# Main.net
KiCad netlist of a schematic drawn in Altium Designer
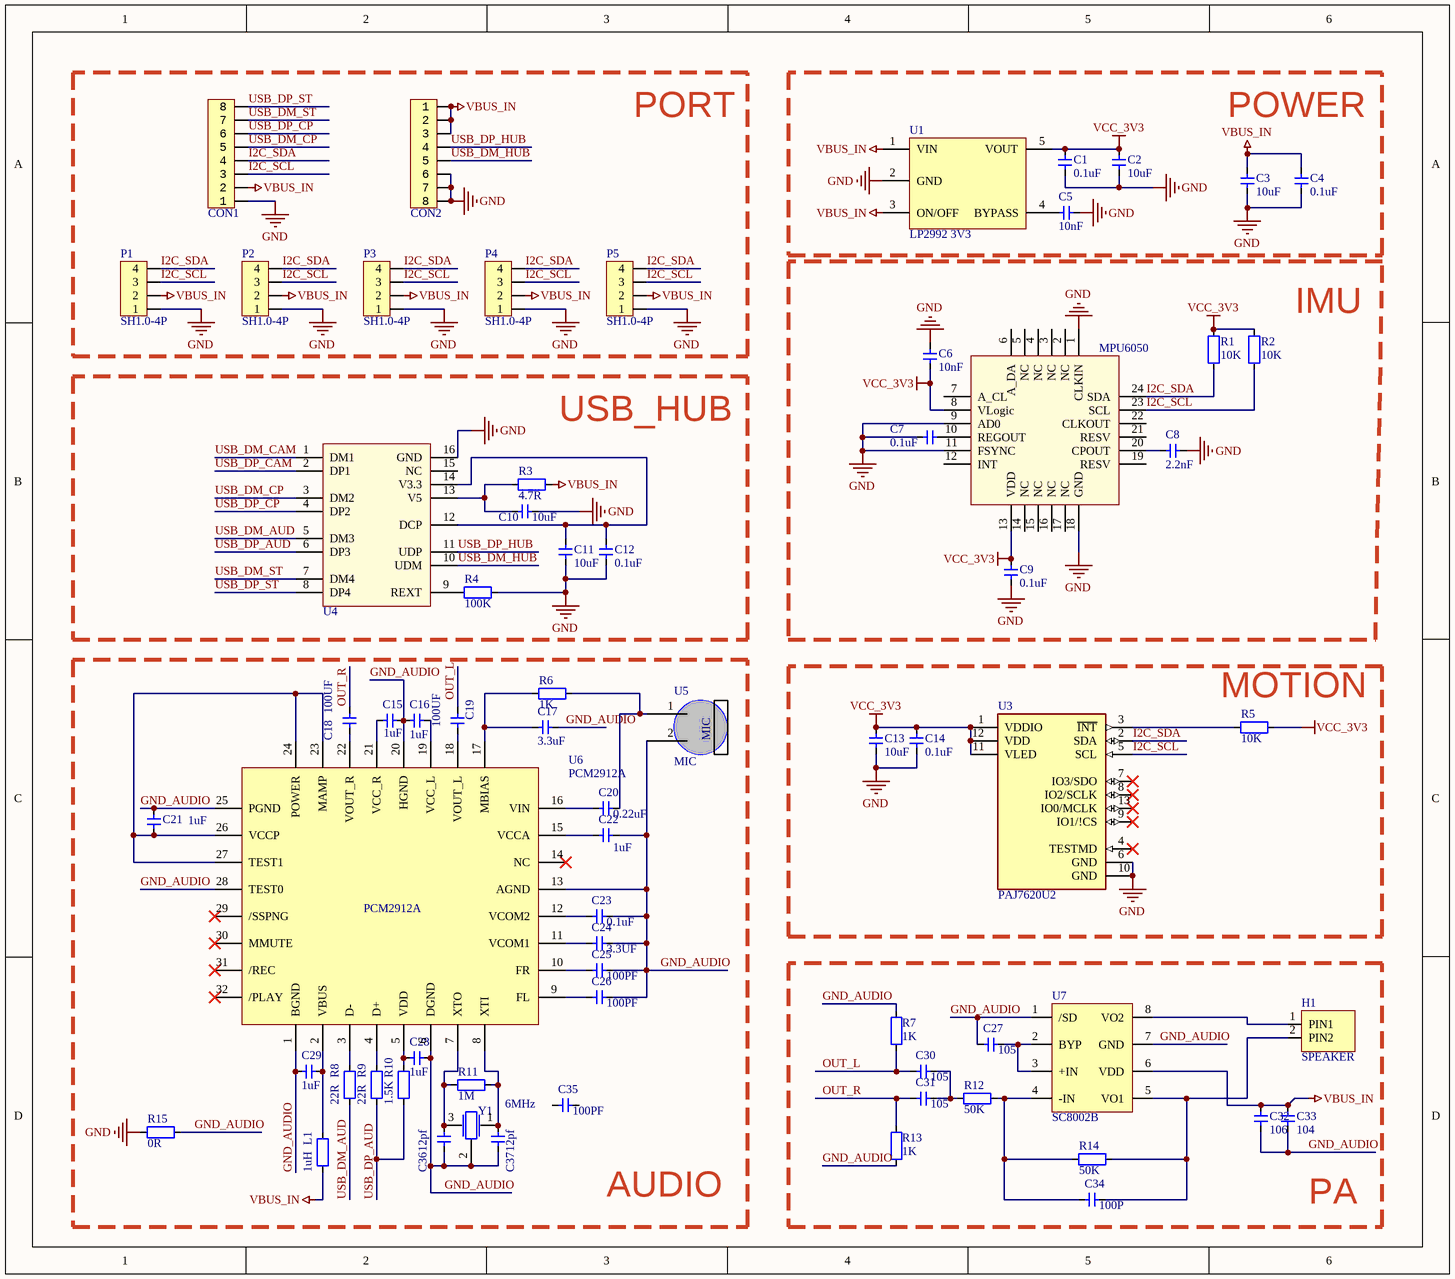
[diagram p0: Main.SchDoc]

(export (version "E")
  (design (tool "Eeschema 10.0.6"))
  (components
    (comp (ref "C1")
      (value "0.1uF")
      (footprint "SensorBoard:CAP_0402")
      (description "Capacitor")
      (libsource (lib "MyPcbLib") (part "电容-0402"))
    )
    (comp (ref "C2")
      (value "10uF")
      (footprint "SensorBoard:CAP_0402")
      (description "Capacitor")
      (libsource (lib "MyPcbLib") (part "电容-0402"))
    )
    (comp (ref "C3")
      (value "10uF")
      (footprint "SensorBoard:CAP_0402")
      (description "Capacitor")
      (libsource (lib "MyPcbLib") (part "电容-0402"))
    )
    (comp (ref "C4")
      (value "0.1uF")
      (footprint "SensorBoard:CAP_0402")
      (description "Capacitor")
      (libsource (lib "MyPcbLib") (part "电容-0402"))
    )
    (comp (ref "C5")
      (value "10nF")
      (footprint "SensorBoard:CAP_0402")
      (description "Capacitor")
      (libsource (lib "MyPcbLib") (part "电容-0402"))
    )
    (comp (ref "C6")
      (value "10nF")
      (footprint "SensorBoard:CAP_0402")
      (description "Capacitor")
      (libsource (lib "MyPcbLib") (part "电容-0402"))
    )
    (comp (ref "C7")
      (value "0.1uF")
      (footprint "SensorBoard:CAP_0402")
      (description "Capacitor")
      (libsource (lib "MyPcbLib") (part "电容-0402"))
    )
    (comp (ref "C8")
      (value "2.2nF")
      (footprint "SensorBoard:CAP_0402")
      (description "Capacitor")
      (libsource (lib "MyPcbLib") (part "电容-0402"))
    )
    (comp (ref "C9")
      (value "0.1uF")
      (footprint "SensorBoard:CAP_0402")
      (description "Capacitor")
      (libsource (lib "MyPcbLib") (part "电容-0402"))
    )
    (comp (ref "C10")
      (value "10uF")
      (footprint "SensorBoard:CAP_0402")
      (description "Capacitor")
      (libsource (lib "MyPcbLib") (part "电容-0402"))
    )
    (comp (ref "C11")
      (value "10uF")
      (footprint "SensorBoard:CAP_0402")
      (description "Capacitor")
      (libsource (lib "MyPcbLib") (part "电容-0402"))
    )
    (comp (ref "C12")
      (value "0.1uF")
      (footprint "SensorBoard:CAP_0402")
      (description "Capacitor")
      (libsource (lib "MyPcbLib") (part "电容-0402"))
    )
    (comp (ref "C13")
      (value "10uF")
      (footprint "SensorBoard:CAP_0402")
      (description "Capacitor")
      (libsource (lib "MyPcbLib") (part "电容-0402"))
    )
    (comp (ref "C14")
      (value "0.1uF")
      (footprint "SensorBoard:CAP_0402")
      (description "Capacitor")
      (libsource (lib "MyPcbLib") (part "电容-0402"))
    )
    (comp (ref "C15")
      (value "1uF")
      (footprint "SensorBoard:CAP_0402")
      (description "Capacitor")
      (libsource (lib "MyPcbLib") (part "电容-0402"))
    )
    (comp (ref "C16")
      (value "1uF")
      (footprint "SensorBoard:CAP_0402")
      (description "Capacitor")
      (libsource (lib "MyPcbLib") (part "电容-0402"))
    )
    (comp (ref "C17")
      (value "3.3uF")
      (footprint "SensorBoard:CAP_0402")
      (description "Capacitor")
      (libsource (lib "MyPcbLib") (part "电容-0402"))
    )
    (comp (ref "C18")
      (value "100UF")
      (footprint "MINI-copter:3225_C")
      (description "Capacitor")
      (libsource (lib "MyPcbLib") (part "电容-0402"))
    )
    (comp (ref "C19")
      (value "100UF")
      (footprint "MINI-copter:3225_C")
      (description "Capacitor")
      (libsource (lib "MyPcbLib") (part "电容-0402"))
    )
    (comp (ref "C20")
      (value "0.22uF")
      (footprint "SensorBoard:CAP_0402")
      (description "Capacitor")
      (libsource (lib "MyPcbLib") (part "电容-0402"))
    )
    (comp (ref "C21")
      (value "1uF")
      (footprint "SensorBoard:CAP_0402")
      (description "Capacitor")
      (libsource (lib "MyPcbLib") (part "电容-0402"))
    )
    (comp (ref "C22")
      (value "1uF")
      (footprint "SensorBoard:CAP_0402")
      (description "Capacitor")
      (libsource (lib "MyPcbLib") (part "电容-0402"))
    )
    (comp (ref "C23")
      (value "0.1uF")
      (footprint "SensorBoard:CAP_0402")
      (description "Capacitor")
      (libsource (lib "MyPcbLib") (part "电容-0402"))
    )
    (comp (ref "C24")
      (value "3.3UF")
      (footprint "SensorBoard:CAP_0402")
      (description "Capacitor")
      (libsource (lib "MyPcbLib") (part "电容-0402"))
    )
    (comp (ref "C25")
      (value "100PF")
      (footprint "SensorBoard:CAP_0402")
      (description "Capacitor")
      (libsource (lib "MyPcbLib") (part "电容-0402"))
    )
    (comp (ref "C26")
      (value "100PF")
      (footprint "SensorBoard:CAP_0402")
      (description "Capacitor")
      (libsource (lib "MyPcbLib") (part "电容-0402"))
    )
    (comp (ref "C27")
      (value "105")
      (footprint "SensorBoard:CAP_0402")
      (description "Capacitor")
      (libsource (lib "MyPcbLib") (part "电容-0402"))
    )
    (comp (ref "C28")
      (value "1uF")
      (footprint "SensorBoard:CAP_0402")
      (description "Capacitor")
      (libsource (lib "MyPcbLib") (part "电容-0402"))
    )
    (comp (ref "C29")
      (value "1uF")
      (footprint "SensorBoard:CAP_0402")
      (description "Capacitor")
      (libsource (lib "MyPcbLib") (part "电容-0402"))
    )
    (comp (ref "C30")
      (value "105")
      (footprint "SensorBoard:CAP_0402")
      (description "Capacitor")
      (libsource (lib "MyPcbLib") (part "电容-0402"))
    )
    (comp (ref "C31")
      (value "105")
      (footprint "SensorBoard:CAP_0402")
      (description "Capacitor")
      (libsource (lib "MyPcbLib") (part "电容-0402"))
    )
    (comp (ref "C32")
      (value "106")
      (footprint "SensorBoard:CAP_0402")
      (description "Capacitor")
      (libsource (lib "MyPcbLib") (part "电容-0402"))
    )
    (comp (ref "C33")
      (value "104")
      (footprint "SensorBoard:CAP_0402")
      (description "Capacitor")
      (libsource (lib "MyPcbLib") (part "电容-0402"))
    )
    (comp (ref "C34")
      (value "100P")
      (footprint "SensorBoard:CAP_0402")
      (description "Capacitor")
      (libsource (lib "MyPcbLib") (part "电容-0402"))
    )
    (comp (ref "C35")
      (value "100PF")
      (footprint "SensorBoard:CAP_0402")
      (description "Capacitor")
      (libsource (lib "MyPcbLib") (part "电容-0402"))
    )
    (comp (ref "C36")
      (value "12pf")
      (footprint "SensorBoard:CAP_0402")
      (description "Capacitor")
      (libsource (lib "MyPcbLib") (part "电容-0402"))
    )
    (comp (ref "C37")
      (value "12pf")
      (footprint "SensorBoard:CAP_0402")
      (description "Capacitor")
      (libsource (lib "MyPcbLib") (part "电容-0402"))
    )
    (comp (ref "CON1")
      (value "FFC_0.5_8")
      (footprint "SensorBoard:FFC_0.5_8")
      (description "FFC")
      (libsource (lib "KitSprout") (part "FFC_0.5_8"))
    )
    (comp (ref "CON2")
      (value "FFC_0.5_8")
      (footprint "SensorBoard:FFC_0.5_8")
      (description "FFC")
      (libsource (lib "") (part "FFC_0.5_8_1"))
    )
    (comp (ref "H1")
      (value "SPEAKER")
      (footprint "ElectronBot:header2p_1.0")
      (libsource (lib "MINI-copter") (part "HEADER-2P"))
    )
    (comp (ref "L1")
      (value "1uH")
      (footprint "SensorBoard:RES_0402")
      (description "Resistor")
      (libsource (lib "") (part "电阻-0402_2"))
    )
    (comp (ref "P1")
      (value "SH1.0-4P")
      (footprint "SensorBoard:SH1.0-4P")
      (libsource (lib "MyPcbLib") (part "SH1.0-4P"))
    )
    (comp (ref "P2")
      (value "SH1.0-4P")
      (footprint "SensorBoard:SH1.0-4P")
      (libsource (lib "MyPcbLib") (part "SH1.0-4P"))
    )
    (comp (ref "P3")
      (value "SH1.0-4P")
      (footprint "SensorBoard:SH1.0-4P")
      (libsource (lib "MyPcbLib") (part "SH1.0-4P"))
    )
    (comp (ref "P4")
      (value "SH1.0-4P")
      (footprint "SensorBoard:SH1.0-4P")
      (libsource (lib "MyPcbLib") (part "SH1.0-4P"))
    )
    (comp (ref "P5")
      (value "SH1.0-4P")
      (footprint "SensorBoard:SH1.0-4P")
      (libsource (lib "MyPcbLib") (part "SH1.0-4P"))
    )
    (comp (ref "R1")
      (value "10K")
      (footprint "SensorBoard:RES_0402")
      (description "Resistor")
      (libsource (lib "") (part "电阻-0402_1"))
    )
    (comp (ref "R2")
      (value "10K")
      (footprint "SensorBoard:RES_0402")
      (description "Resistor")
      (libsource (lib "") (part "电阻-0402_1"))
    )
    (comp (ref "R3")
      (value "4.7R")
      (footprint "SensorBoard:RES_0402")
      (description "Resistor")
      (libsource (lib "") (part "电阻-0402_3"))
    )
    (comp (ref "R4")
      (value "100K")
      (footprint "SensorBoard:RES_0402")
      (description "Resistor")
      (libsource (lib "") (part "电阻-0402_3"))
    )
    (comp (ref "R5")
      (value "10K")
      (footprint "SensorBoard:RES_0402")
      (description "Resistor")
      (libsource (lib "MyPcbLib") (part "电阻-0402"))
    )
    (comp (ref "R6")
      (value "1K")
      (footprint "SensorBoard:RES_0402")
      (description "Resistor")
      (libsource (lib "MyPcbLib") (part "电阻-0402"))
    )
    (comp (ref "R7")
      (value "1K")
      (footprint "SensorBoard:RES_0402")
      (description "Resistor")
      (libsource (lib "") (part "电阻-0402_2"))
    )
    (comp (ref "R8")
      (value "22R")
      (footprint "SensorBoard:RES_0402")
      (description "Resistor")
      (libsource (lib "") (part "电阻-0402_2"))
    )
    (comp (ref "R9")
      (value "22R")
      (footprint "SensorBoard:RES_0402")
      (description "Resistor")
      (libsource (lib "") (part "电阻-0402_2"))
    )
    (comp (ref "R10")
      (value "1.5K")
      (footprint "SensorBoard:RES_0402")
      (description "Resistor")
      (libsource (lib "") (part "电阻-0402_2"))
    )
    (comp (ref "R11")
      (value "1M")
      (footprint "SensorBoard:RES_0402")
      (description "Resistor")
      (libsource (lib "MyPcbLib") (part "电阻-0402"))
    )
    (comp (ref "R12")
      (value "50K")
      (footprint "SensorBoard:RES_0402")
      (description "Resistor")
      (libsource (lib "MyPcbLib") (part "电阻-0402"))
    )
    (comp (ref "R13")
      (value "1K")
      (footprint "SensorBoard:RES_0402")
      (description "Resistor")
      (libsource (lib "") (part "电阻-0402_1"))
    )
    (comp (ref "R14")
      (value "50K")
      (footprint "SensorBoard:RES_0402")
      (description "Resistor")
      (libsource (lib "MyPcbLib") (part "电阻-0402"))
    )
    (comp (ref "R15")
      (value "0R")
      (footprint "SensorBoard:RES_0402")
      (description "Resistor")
      (libsource (lib "MyPcbLib") (part "电阻-0402"))
    )
    (comp (ref "U1")
      (value "LP2992 3V3")
      (footprint "SensorBoard:SOT23-5")
      (description "LDO")
      (libsource (lib "MyPcbLib") (part "LP2992"))
    )
    (comp (ref "U2")
      (value "MPU6050")
      (footprint "QFN-24")
      (description "六轴传感器")
      (libsource (lib "mLib") (part "MPU6050"))
    )
    (comp (ref "U3")
      (value "PAJ7620U2")
      (footprint "SensorBoard:PAJ7620U2")
      (description "module sensorPAJ7620U2 : 54/TRAY, 5400/BOX, 32400/CARTON")
      (fields (field (name "MF") "Pixart"))
      (libsource (lib "MyPcbLib") (part "PAJ7620U2"))
    )
    (comp (ref "U4")
      (value "HS8836A")
      (footprint "SensorBoard:SO-16N")
      (description "USB2.0 HUB")
      (libsource (lib "MyPcbLib") (part "HS8836A"))
    )
    (comp (ref "U5") (value "MIC") (footprint "Voice:MIC6*2.2") (libsource (lib "voice") (part "MIC")))
    (comp (ref "U6")
      (value "PCM2912A")
      (footprint "Voice:PCM2912")
      (libsource (lib "voice") (part "PCM2912A"))
    )
    (comp (ref "U7") (value "SC8002B") (footprint "Voice:SOP-8") (libsource (lib "voice") (part "SC8002B")))
    (comp (ref "Y1")
      (value "6MHz")
      (footprint "MINI-copter:cystal-3P -4520")
      (description "村田贴片")
      (libsource (lib "MyPcbLib") (part "晶振-3Pin"))
    )
  )
  (nets
    (net (code "2") (name "/GND_AUDIO") (class "Default")
      (node (ref "C15") (pin "2") (pinfunction "2_2") (pintype "passive"))
      (node (ref "C16") (pin "2") (pinfunction "2_2") (pintype "passive"))
      (node (ref "C17") (pin "2") (pinfunction "2_2") (pintype "passive"))
      (node (ref "C21") (pin "2") (pinfunction "2_2") (pintype "passive"))
      (node (ref "C22") (pin "2") (pinfunction "2_2") (pintype "passive"))
      (node (ref "C23") (pin "1") (pinfunction "1_1") (pintype "passive"))
      (node (ref "C24") (pin "1") (pinfunction "1_1") (pintype "passive"))
      (node (ref "C25") (pin "1") (pinfunction "1_1") (pintype "passive"))
      (node (ref "C26") (pin "1") (pinfunction "1_1") (pintype "passive"))
      (node (ref "C27") (pin "2") (pinfunction "2_2") (pintype "passive"))
      (node (ref "C28") (pin "1") (pinfunction "1_1") (pintype "passive"))
      (node (ref "C29") (pin "2") (pinfunction "2_2") (pintype "passive"))
      (node (ref "C32") (pin "2") (pinfunction "2_2") (pintype "passive"))
      (node (ref "C33") (pin "2") (pinfunction "2_2") (pintype "passive"))
      (node (ref "C36") (pin "2") (pinfunction "2_2") (pintype "passive"))
      (node (ref "C37") (pin "2") (pinfunction "2_2") (pintype "passive"))
      (node (ref "R13") (pin "1") (pinfunction "1_1") (pintype "passive"))
      (node (ref "R15") (pin "2") (pinfunction "2_2") (pintype "passive"))
      (node (ref "R7") (pin "1") (pinfunction "1_1") (pintype "passive"))
      (node (ref "U5") (pin "2") (pintype "passive"))
      (node (ref "U6") (pin "1") (pinfunction "BGND_1") (pintype "passive"))
      (node (ref "U6") (pin "13") (pinfunction "AGND_13") (pintype "passive"))
      (node (ref "U6") (pin "20") (pinfunction "HGND_20") (pintype "passive"))
      (node (ref "U6") (pin "25") (pinfunction "PGND_25") (pintype "passive"))
      (node (ref "U6") (pin "28") (pinfunction "TEST0_28") (pintype "passive"))
      (node (ref "U6") (pin "6") (pinfunction "DGND_6") (pintype "passive"))
      (node (ref "U7") (pin "1") (pinfunction "/SD_1") (pintype "passive"))
      (node (ref "U7") (pin "7") (pinfunction "GND_7") (pintype "passive"))
      (node (ref "Y1") (pin "2") (pinfunction "2_2") (pintype "passive"))
    )
    (net (code "3") (name "/I2C_SCL") (class "Default")
      (node (ref "CON1") (pin "3") (pinfunction "3_3") (pintype "passive"))
      (node (ref "P1") (pin "3") (pinfunction "3_3") (pintype "passive"))
      (node (ref "P2") (pin "3") (pinfunction "3_3") (pintype "passive"))
      (node (ref "P3") (pin "3") (pinfunction "3_3") (pintype "passive"))
      (node (ref "P4") (pin "3") (pinfunction "3_3") (pintype "passive"))
      (node (ref "P5") (pin "3") (pinfunction "3_3") (pintype "passive"))
      (node (ref "R2") (pin "1") (pinfunction "1_1") (pintype "passive"))
      (node (ref "U2") (pin "23") (pinfunction "SCL_23") (pintype "passive"))
      (node (ref "U3") (pin "5") (pinfunction "SCL_5") (pintype "input"))
    )
    (net (code "4") (name "/I2C_SDA") (class "Default")
      (node (ref "CON1") (pin "4") (pinfunction "4_4") (pintype "passive"))
      (node (ref "P1") (pin "4") (pinfunction "4_4") (pintype "passive"))
      (node (ref "P2") (pin "4") (pinfunction "4_4") (pintype "passive"))
      (node (ref "P3") (pin "4") (pinfunction "4_4") (pintype "passive"))
      (node (ref "P4") (pin "4") (pinfunction "4_4") (pintype "passive"))
      (node (ref "P5") (pin "4") (pinfunction "4_4") (pintype "passive"))
      (node (ref "R1") (pin "1") (pinfunction "1_1") (pintype "passive"))
      (node (ref "U2") (pin "24") (pinfunction "SDA_24") (pintype "passive"))
      (node (ref "U3") (pin "2") (pinfunction "SDA_2") (pintype "bidirectional"))
    )
    (net (code "5") (name "/OUT_L") (class "Default")
      (node (ref "C19") (pin "2") (pinfunction "2_2") (pintype "passive"))
      (node (ref "C30") (pin "2") (pinfunction "2_2") (pintype "passive"))
      (node (ref "R7") (pin "2") (pinfunction "2_2") (pintype "passive"))
    )
    (net (code "6") (name "/OUT_R") (class "Default")
      (node (ref "C18") (pin "2") (pinfunction "2_2") (pintype "passive"))
      (node (ref "C31") (pin "2") (pinfunction "2_2") (pintype "passive"))
      (node (ref "R13") (pin "2") (pinfunction "2_2") (pintype "passive"))
    )
    (net (code "7") (name "/USB_DM_AUD") (class "Default")
      (node (ref "R8") (pin "2") (pinfunction "2_2") (pintype "passive"))
      (node (ref "U4") (pin "5") (pinfunction "DM3_5") (pintype "passive"))
    )
    (net (code "8") (name "/USB_DM_CAM") (class "Default")
      (node (ref "U4") (pin "1") (pinfunction "DM1_1") (pintype "passive"))
    )
    (net (code "9") (name "/USB_DM_CP") (class "Default")
      (node (ref "CON1") (pin "5") (pinfunction "5_5") (pintype "passive"))
      (node (ref "U4") (pin "3") (pinfunction "DM2_3") (pintype "passive"))
    )
    (net (code "10") (name "/USB_DM_HUB") (class "Default")
      (node (ref "CON2") (pin "5") (pinfunction "5_5") (pintype "passive"))
      (node (ref "U4") (pin "10") (pinfunction "UDM_10") (pintype "passive"))
    )
    (net (code "11") (name "/USB_DM_ST") (class "Default")
      (node (ref "CON1") (pin "7") (pinfunction "7_7") (pintype "passive"))
      (node (ref "U4") (pin "7") (pinfunction "DM4_7") (pintype "passive"))
    )
    (net (code "12") (name "/USB_DP_AUD") (class "Default")
      (node (ref "R10") (pin "2") (pinfunction "2_2") (pintype "passive"))
      (node (ref "R9") (pin "2") (pinfunction "2_2") (pintype "passive"))
      (node (ref "U4") (pin "6") (pinfunction "DP3_6") (pintype "passive"))
    )
    (net (code "13") (name "/USB_DP_CAM") (class "Default")
      (node (ref "U4") (pin "2") (pinfunction "DP1_2") (pintype "passive"))
    )
    (net (code "14") (name "/USB_DP_CP") (class "Default")
      (node (ref "CON1") (pin "6") (pinfunction "6_6") (pintype "passive"))
      (node (ref "U4") (pin "4") (pinfunction "DP2_4") (pintype "passive"))
    )
    (net (code "15") (name "/USB_DP_HUB") (class "Default")
      (node (ref "CON2") (pin "4") (pinfunction "4_4") (pintype "passive"))
      (node (ref "U4") (pin "11") (pinfunction "UDP_11") (pintype "passive"))
    )
    (net (code "16") (name "/USB_DP_ST") (class "Default")
      (node (ref "CON1") (pin "8") (pinfunction "8_8") (pintype "passive"))
      (node (ref "U4") (pin "8") (pinfunction "DP4_8") (pintype "passive"))
    )
    (net (code "17") (name "GND") (class "Default")
      (node (ref "C1") (pin "1") (pinfunction "1_1") (pintype "passive"))
      (node (ref "C10") (pin "1") (pinfunction "1_1") (pintype "passive"))
      (node (ref "C11") (pin "2") (pinfunction "2_2") (pintype "passive"))
      (node (ref "C12") (pin "2") (pinfunction "2_2") (pintype "passive"))
      (node (ref "C13") (pin "2") (pinfunction "2_2") (pintype "passive"))
      (node (ref "C14") (pin "2") (pinfunction "2_2") (pintype "passive"))
      (node (ref "C2") (pin "1") (pinfunction "1_1") (pintype "passive"))
      (node (ref "C3") (pin "1") (pinfunction "1_1") (pintype "passive"))
      (node (ref "C4") (pin "1") (pinfunction "1_1") (pintype "passive"))
      (node (ref "C5") (pin "1") (pinfunction "1_1") (pintype "passive"))
      (node (ref "C6") (pin "2") (pinfunction "2_2") (pintype "passive"))
      (node (ref "C7") (pin "2") (pinfunction "2_2") (pintype "passive"))
      (node (ref "C8") (pin "1") (pinfunction "1_1") (pintype "passive"))
      (node (ref "C9") (pin "1") (pinfunction "1_1") (pintype "passive"))
      (node (ref "CON1") (pin "1") (pinfunction "1_1") (pintype "passive"))
      (node (ref "CON2") (pin "6") (pinfunction "6_6") (pintype "passive"))
      (node (ref "CON2") (pin "7") (pinfunction "7_7") (pintype "passive"))
      (node (ref "CON2") (pin "8") (pinfunction "8_8") (pintype "passive"))
      (node (ref "P1") (pin "1") (pinfunction "1_1") (pintype "passive"))
      (node (ref "P2") (pin "1") (pinfunction "1_1") (pintype "passive"))
      (node (ref "P3") (pin "1") (pinfunction "1_1") (pintype "passive"))
      (node (ref "P4") (pin "1") (pinfunction "1_1") (pintype "passive"))
      (node (ref "P5") (pin "1") (pinfunction "1_1") (pintype "passive"))
      (node (ref "R15") (pin "1") (pinfunction "1_1") (pintype "passive"))
      (node (ref "R4") (pin "1") (pinfunction "1_1") (pintype "passive"))
      (node (ref "U1") (pin "2") (pinfunction "GND_2") (pintype "passive"))
      (node (ref "U2") (pin "1") (pinfunction "CLKIN_1") (pintype "passive"))
      (node (ref "U2") (pin "11") (pinfunction "FSYNC_11") (pintype "passive"))
      (node (ref "U2") (pin "18") (pinfunction "GND_18") (pintype "passive"))
      (node (ref "U2") (pin "9") (pinfunction "AD0_9") (pintype "passive"))
      (node (ref "U3") (pin "10") (pinfunction "GND_10") (pintype "passive"))
      (node (ref "U3") (pin "6") (pinfunction "GND_6") (pintype "passive"))
      (node (ref "U4") (pin "16") (pinfunction "GND_16") (pintype "passive"))
    )
    (net (code "18") (name "Net-(C20-Pad2)") (class "Default")
      (node (ref "C20") (pin "2") (pinfunction "2_2") (pintype "passive"))
      (node (ref "R6") (pin "2") (pinfunction "2_2") (pintype "passive"))
      (node (ref "U5") (pin "1") (pintype "passive"))
    )
    (net (code "19") (name "Net-(C30-Pad1)") (class "Default")
      (node (ref "C30") (pin "1") (pinfunction "1_1") (pintype "passive"))
      (node (ref "C31") (pin "1") (pinfunction "1_1") (pintype "passive"))
      (node (ref "R12") (pin "1") (pinfunction "1_1") (pintype "passive"))
    )
    (net (code "20") (name "Net-(H1-PIN1)") (class "Default")
      (node (ref "H1") (pin "1") (pinfunction "PIN1_1") (pintype "passive"))
      (node (ref "U7") (pin "8") (pinfunction "VO2_8") (pintype "passive"))
    )
    (net (code "21") (name "Net-(H1-PIN2)") (class "Default")
      (node (ref "C34") (pin "1") (pinfunction "1_1") (pintype "passive"))
      (node (ref "H1") (pin "2") (pinfunction "PIN2_2") (pintype "passive"))
      (node (ref "R14") (pin "2") (pinfunction "2_2") (pintype "passive"))
      (node (ref "U7") (pin "5") (pinfunction "VO1_5") (pintype "passive"))
    )
    (net (code "22") (name "Net-(U1-BYPASS)") (class "Default")
      (node (ref "C5") (pin "2") (pinfunction "2_2") (pintype "passive"))
      (node (ref "U1") (pin "4") (pinfunction "BYPASS_4") (pintype "passive"))
    )
    (net (code "23") (name "Net-(U2-CPOUT)") (class "Default")
      (node (ref "C8") (pin "2") (pinfunction "2_2") (pintype "passive"))
      (node (ref "U2") (pin "20") (pinfunction "CPOUT_20") (pintype "passive"))
    )
    (net (code "24") (name "Net-(U2-REGOUT)") (class "Default")
      (node (ref "C7") (pin "1") (pinfunction "1_1") (pintype "passive"))
      (node (ref "U2") (pin "10") (pinfunction "REGOUT_10") (pintype "passive"))
    )
    (net (code "25") (name "Net-(U3-~{INT})") (class "Default")
      (node (ref "R5") (pin "1") (pinfunction "1_1") (pintype "passive"))
      (node (ref "U3") (pin "3") (pinfunction "~{INT}_3") (pintype "output"))
    )
    (net (code "26") (name "Net-(U4-DCP)") (class "Default")
      (node (ref "C11") (pin "1") (pinfunction "1_1") (pintype "passive"))
      (node (ref "C12") (pin "1") (pinfunction "1_1") (pintype "passive"))
      (node (ref "U4") (pin "12") (pinfunction "DCP_12") (pintype "passive"))
      (node (ref "U4") (pin "14") (pinfunction "V3.3_14") (pintype "passive"))
    )
    (net (code "27") (name "Net-(U4-REXT)") (class "Default")
      (node (ref "R4") (pin "2") (pinfunction "2_2") (pintype "passive"))
      (node (ref "U4") (pin "9") (pinfunction "REXT_9") (pintype "passive"))
    )
    (net (code "28") (name "Net-(U4-V5)") (class "Default")
      (node (ref "C10") (pin "2") (pinfunction "2_2") (pintype "passive"))
      (node (ref "R3") (pin "2") (pinfunction "2_2") (pintype "passive"))
      (node (ref "U4") (pin "13") (pinfunction "V5_13") (pintype "passive"))
    )
    (net (code "29") (name "Net-(U6-D+)") (class "Default")
      (node (ref "R9") (pin "1") (pinfunction "1_1") (pintype "passive"))
      (node (ref "U6") (pin "4") (pinfunction "D+_4") (pintype "passive"))
    )
    (net (code "30") (name "Net-(U6-D-)") (class "Default")
      (node (ref "R8") (pin "1") (pinfunction "1_1") (pintype "passive"))
      (node (ref "U6") (pin "3") (pinfunction "D-_3") (pintype "passive"))
    )
    (net (code "31") (name "Net-(U6-FL)") (class "Default")
      (node (ref "C26") (pin "2") (pinfunction "2_2") (pintype "passive"))
      (node (ref "U6") (pin "9") (pinfunction "FL_9") (pintype "passive"))
    )
    (net (code "32") (name "Net-(U6-FR)") (class "Default")
      (node (ref "C25") (pin "2") (pinfunction "2_2") (pintype "passive"))
      (node (ref "U6") (pin "10") (pinfunction "FR_10") (pintype "passive"))
    )
    (net (code "33") (name "Net-(U6-MAMP)") (class "Default")
      (node (ref "C21") (pin "1") (pinfunction "1_1") (pintype "passive"))
      (node (ref "U6") (pin "23") (pinfunction "MAMP_23") (pintype "passive"))
      (node (ref "U6") (pin "24") (pinfunction "POWER_24") (pintype "passive"))
      (node (ref "U6") (pin "26") (pinfunction "VCCP_26") (pintype "passive"))
      (node (ref "U6") (pin "27") (pinfunction "TEST1_27") (pintype "passive"))
    )
    (net (code "34") (name "Net-(U6-MBIAS)") (class "Default")
      (node (ref "C17") (pin "1") (pinfunction "1_1") (pintype "passive"))
      (node (ref "R6") (pin "1") (pinfunction "1_1") (pintype "passive"))
      (node (ref "U6") (pin "17") (pinfunction "MBIAS_17") (pintype "passive"))
    )
    (net (code "35") (name "Net-(U6-VBUS)") (class "Default")
      (node (ref "C29") (pin "1") (pinfunction "1_1") (pintype "passive"))
      (node (ref "L1") (pin "1") (pinfunction "1_1") (pintype "passive"))
      (node (ref "U6") (pin "2") (pinfunction "VBUS_2") (pintype "passive"))
    )
    (net (code "36") (name "Net-(U6-VCCA)") (class "Default")
      (node (ref "C22") (pin "1") (pinfunction "1_1") (pintype "passive"))
      (node (ref "U6") (pin "15") (pinfunction "VCCA_15") (pintype "passive"))
    )
    (net (code "37") (name "Net-(U6-VCC_L)") (class "Default")
      (node (ref "C16") (pin "1") (pinfunction "1_1") (pintype "passive"))
      (node (ref "U6") (pin "19") (pinfunction "VCC_L_19") (pintype "passive"))
    )
    (net (code "38") (name "Net-(U6-VCC_R)") (class "Default")
      (node (ref "C15") (pin "1") (pinfunction "1_1") (pintype "passive"))
      (node (ref "U6") (pin "21") (pinfunction "VCC_R_21") (pintype "passive"))
    )
    (net (code "39") (name "Net-(U6-VCOM1)") (class "Default")
      (node (ref "C24") (pin "2") (pinfunction "2_2") (pintype "passive"))
      (node (ref "U6") (pin "11") (pinfunction "VCOM1_11") (pintype "passive"))
    )
    (net (code "40") (name "Net-(U6-VCOM2)") (class "Default")
      (node (ref "C23") (pin "2") (pinfunction "2_2") (pintype "passive"))
      (node (ref "U6") (pin "12") (pinfunction "VCOM2_12") (pintype "passive"))
    )
    (net (code "41") (name "Net-(U6-VDD)") (class "Default")
      (node (ref "C28") (pin "2") (pinfunction "2_2") (pintype "passive"))
      (node (ref "R10") (pin "1") (pinfunction "1_1") (pintype "passive"))
      (node (ref "U6") (pin "5") (pinfunction "VDD_5") (pintype "passive"))
    )
    (net (code "42") (name "Net-(U6-VIN)") (class "Default")
      (node (ref "C20") (pin "1") (pinfunction "1_1") (pintype "passive"))
      (node (ref "U6") (pin "16") (pinfunction "VIN_16") (pintype "passive"))
    )
    (net (code "43") (name "Net-(U6-VOUT_L)") (class "Default")
      (node (ref "C19") (pin "1") (pinfunction "1_1") (pintype "passive"))
      (node (ref "U6") (pin "18") (pinfunction "VOUT_L_18") (pintype "passive"))
    )
    (net (code "44") (name "Net-(U6-VOUT_R)") (class "Default")
      (node (ref "C18") (pin "1") (pinfunction "1_1") (pintype "passive"))
      (node (ref "U6") (pin "22") (pinfunction "VOUT_R_22") (pintype "passive"))
    )
    (net (code "45") (name "Net-(U6-XTI)") (class "Default")
      (node (ref "C37") (pin "1") (pinfunction "1_1") (pintype "passive"))
      (node (ref "R11") (pin "2") (pinfunction "2_2") (pintype "passive"))
      (node (ref "U6") (pin "8") (pinfunction "XTI_8") (pintype "passive"))
      (node (ref "Y1") (pin "1") (pinfunction "1_1") (pintype "passive"))
    )
    (net (code "46") (name "Net-(U6-XTO)") (class "Default")
      (node (ref "C36") (pin "1") (pinfunction "1_1") (pintype "passive"))
      (node (ref "R11") (pin "1") (pinfunction "1_1") (pintype "passive"))
      (node (ref "U6") (pin "7") (pinfunction "XTO_7") (pintype "passive"))
      (node (ref "Y1") (pin "3") (pinfunction "3_3") (pintype "passive"))
    )
    (net (code "47") (name "Net-(U7-+IN)") (class "Default")
      (node (ref "C27") (pin "1") (pinfunction "1_1") (pintype "passive"))
      (node (ref "U7") (pin "2") (pinfunction "BYP_2") (pintype "passive"))
      (node (ref "U7") (pin "3") (pinfunction "+IN_3") (pintype "passive"))
    )
    (net (code "48") (name "Net-(U7--IN)") (class "Default")
      (node (ref "C34") (pin "2") (pinfunction "2_2") (pintype "passive"))
      (node (ref "R12") (pin "2") (pinfunction "2_2") (pintype "passive"))
      (node (ref "R14") (pin "1") (pinfunction "1_1") (pintype "passive"))
      (node (ref "U7") (pin "4") (pinfunction "-IN_4") (pintype "passive"))
    )
    (net (code "49") (name "VBUS_IN") (class "Default")
      (node (ref "C3") (pin "2") (pinfunction "2_2") (pintype "passive"))
      (node (ref "C32") (pin "1") (pinfunction "1_1") (pintype "passive"))
      (node (ref "C33") (pin "1") (pinfunction "1_1") (pintype "passive"))
      (node (ref "C4") (pin "2") (pinfunction "2_2") (pintype "passive"))
      (node (ref "CON1") (pin "2") (pinfunction "2_2") (pintype "passive"))
      (node (ref "CON2") (pin "1") (pinfunction "1_1") (pintype "passive"))
      (node (ref "CON2") (pin "2") (pinfunction "2_2") (pintype "passive"))
      (node (ref "CON2") (pin "3") (pinfunction "3_3") (pintype "passive"))
      (node (ref "L1") (pin "2") (pinfunction "2_2") (pintype "passive"))
      (node (ref "P1") (pin "2") (pinfunction "2_2") (pintype "passive"))
      (node (ref "P2") (pin "2") (pinfunction "2_2") (pintype "passive"))
      (node (ref "P3") (pin "2") (pinfunction "2_2") (pintype "passive"))
      (node (ref "P4") (pin "2") (pinfunction "2_2") (pintype "passive"))
      (node (ref "P5") (pin "2") (pinfunction "2_2") (pintype "passive"))
      (node (ref "R3") (pin "1") (pinfunction "1_1") (pintype "passive"))
      (node (ref "U1") (pin "1") (pinfunction "VIN_1") (pintype "passive"))
      (node (ref "U1") (pin "3") (pinfunction "ON/OFF_3") (pintype "passive"))
      (node (ref "U7") (pin "6") (pinfunction "VDD_6") (pintype "passive"))
    )
    (net (code "50") (name "VCC_3V3") (class "Default")
      (node (ref "C1") (pin "2") (pinfunction "2_2") (pintype "passive"))
      (node (ref "C13") (pin "1") (pinfunction "1_1") (pintype "passive"))
      (node (ref "C14") (pin "1") (pinfunction "1_1") (pintype "passive"))
      (node (ref "C2") (pin "2") (pinfunction "2_2") (pintype "passive"))
      (node (ref "C6") (pin "1") (pinfunction "1_1") (pintype "passive"))
      (node (ref "C9") (pin "2") (pinfunction "2_2") (pintype "passive"))
      (node (ref "R1") (pin "2") (pinfunction "2_2") (pintype "passive"))
      (node (ref "R2") (pin "2") (pinfunction "2_2") (pintype "passive"))
      (node (ref "R5") (pin "2") (pinfunction "2_2") (pintype "passive"))
      (node (ref "U1") (pin "5") (pinfunction "VOUT_5") (pintype "passive"))
      (node (ref "U2") (pin "13") (pinfunction "VDD_13") (pintype "passive"))
      (node (ref "U2") (pin "8") (pinfunction "VLogic_8") (pintype "passive"))
      (node (ref "U3") (pin "1") (pinfunction "VDDIO_1") (pintype "power_in"))
      (node (ref "U3") (pin "11") (pinfunction "VLED_11") (pintype "power_in"))
      (node (ref "U3") (pin "12") (pinfunction "VDD_12") (pintype "power_in"))
    )
    (net (code "51") (name "unconnected-(C35-Pad1)") (class "Default")
      (node (ref "C35") (pin "1") (pinfunction "1_1") (pintype "passive"))
    )
    (net (code "52") (name "unconnected-(C35-Pad2)") (class "Default")
      (node (ref "C35") (pin "2") (pinfunction "2_2") (pintype "passive"))
    )
    (net (code "53") (name "unconnected-(U2-A_CL-Pad7)") (class "Default")
      (node (ref "U2") (pin "7") (pinfunction "A_CL_7") (pintype "passive"))
    )
    (net (code "54") (name "unconnected-(U2-A_DA-Pad6)") (class "Default")
      (node (ref "U2") (pin "6") (pinfunction "A_DA_6") (pintype "passive"))
    )
    (net (code "55") (name "unconnected-(U2-CLKOUT-Pad22)") (class "Default")
      (node (ref "U2") (pin "22") (pinfunction "CLKOUT_22") (pintype "passive"))
    )
    (net (code "56") (name "unconnected-(U2-INT-Pad12)") (class "Default")
      (node (ref "U2") (pin "12") (pinfunction "INT_12") (pintype "passive"))
    )
    (net (code "57") (name "unconnected-(U2-NC-Pad2)") (class "Default")
      (node (ref "U2") (pin "2") (pinfunction "NC_2") (pintype "passive"))
    )
    (net (code "58") (name "unconnected-(U2-NC-Pad3)") (class "Default")
      (node (ref "U2") (pin "3") (pinfunction "NC_3") (pintype "passive"))
    )
    (net (code "59") (name "unconnected-(U2-NC-Pad4)") (class "Default")
      (node (ref "U2") (pin "4") (pinfunction "NC_4") (pintype "passive"))
    )
    (net (code "60") (name "unconnected-(U2-NC-Pad5)") (class "Default")
      (node (ref "U2") (pin "5") (pinfunction "NC_5") (pintype "passive"))
    )
    (net (code "61") (name "unconnected-(U2-NC-Pad14)") (class "Default")
      (node (ref "U2") (pin "14") (pinfunction "NC_14") (pintype "passive"))
    )
    (net (code "62") (name "unconnected-(U2-NC-Pad15)") (class "Default")
      (node (ref "U2") (pin "15") (pinfunction "NC_15") (pintype "passive"))
    )
    (net (code "63") (name "unconnected-(U2-NC-Pad16)") (class "Default")
      (node (ref "U2") (pin "16") (pinfunction "NC_16") (pintype "passive"))
    )
    (net (code "64") (name "unconnected-(U2-NC-Pad17)") (class "Default")
      (node (ref "U2") (pin "17") (pinfunction "NC_17") (pintype "passive"))
    )
    (net (code "65") (name "unconnected-(U2-RESV-Pad19)") (class "Default")
      (node (ref "U2") (pin "19") (pinfunction "RESV_19") (pintype "passive"))
    )
    (net (code "66") (name "unconnected-(U2-RESV-Pad21)") (class "Default")
      (node (ref "U2") (pin "21") (pinfunction "RESV_21") (pintype "passive"))
    )
    (net (code "67") (name "unconnected-(U3-IO0{slash}MCLK-Pad13)") (class "Default")
      (node (ref "U3") (pin "13") (pinfunction "IO0/MCLK_13") (pintype "bidirectional+no_connect"))
    )
    (net (code "68") (name "unconnected-(U3-IO1{slash}!CS-Pad9)") (class "Default")
      (node (ref "U3") (pin "9") (pinfunction "IO1/!CS_9") (pintype "bidirectional+no_connect"))
    )
    (net (code "69") (name "unconnected-(U3-IO2{slash}SCLK-Pad8)") (class "Default")
      (node (ref "U3") (pin "8") (pinfunction "IO2/SCLK_8") (pintype "bidirectional+no_connect"))
    )
    (net (code "70") (name "unconnected-(U3-IO3{slash}SDO-Pad7)") (class "Default")
      (node (ref "U3") (pin "7") (pinfunction "IO3/SDO_7") (pintype "bidirectional+no_connect"))
    )
    (net (code "71") (name "unconnected-(U3-TESTMD-Pad4)") (class "Default")
      (node (ref "U3") (pin "4") (pinfunction "TESTMD_4") (pintype "input+no_connect"))
    )
    (net (code "72") (name "unconnected-(U4-NC-Pad15)") (class "Default")
      (node (ref "U4") (pin "15") (pinfunction "NC_15") (pintype "passive"))
    )
    (net (code "73") (name "unconnected-(U6-MMUTE-Pad30)") (class "Default")
      (node (ref "U6") (pin "30") (pinfunction "MMUTE_30") (pintype "passive+no_connect"))
    )
    (net (code "74") (name "unconnected-(U6-NC-Pad14)") (class "Default")
      (node (ref "U6") (pin "14") (pinfunction "NC_14") (pintype "passive+no_connect"))
    )
    (net (code "75") (name "unconnected-(U6-{slash}PLAY-Pad32)") (class "Default")
      (node (ref "U6") (pin "32") (pinfunction "/PLAY_32") (pintype "passive+no_connect"))
    )
    (net (code "76") (name "unconnected-(U6-{slash}REC-Pad31)") (class "Default")
      (node (ref "U6") (pin "31") (pinfunction "/REC_31") (pintype "passive+no_connect"))
    )
    (net (code "77") (name "unconnected-(U6-{slash}SSPNG-Pad29)") (class "Default")
      (node (ref "U6") (pin "29") (pinfunction "/SSPNG_29") (pintype "passive+no_connect"))
    )
  )
)
